# CPU.net
KiCad netlist of a schematic drawn in Altium Designer
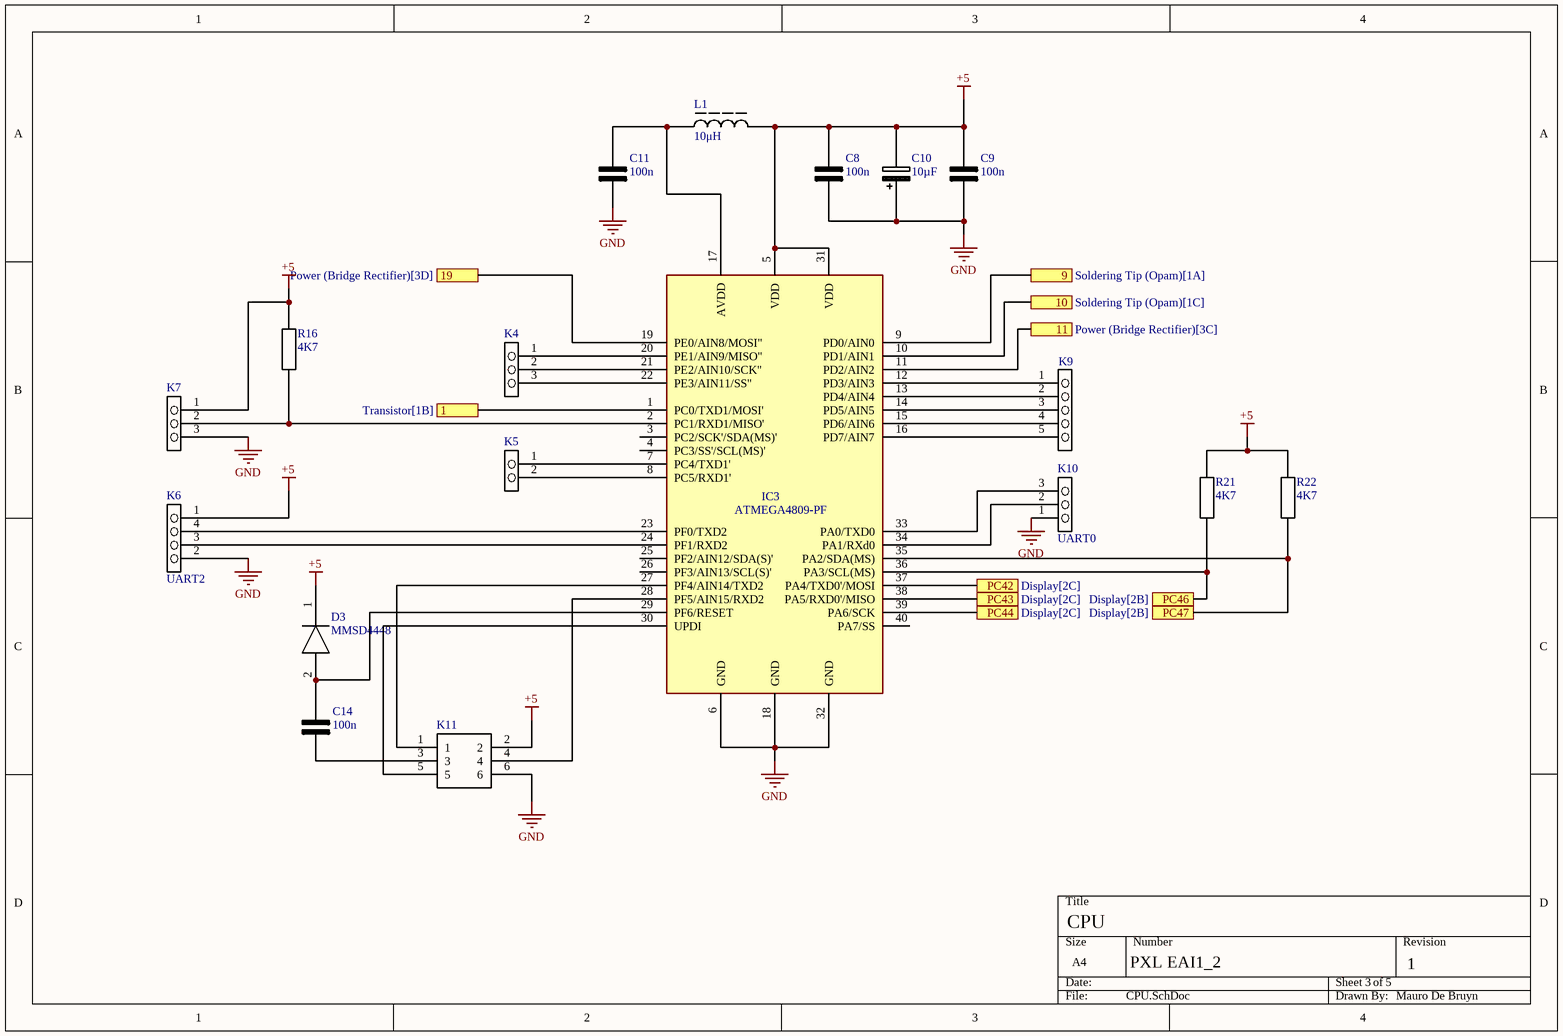
[diagram p0: CPU.SchDoc]

(export (version "E")
  (design (tool "Eeschema 10.0.6"))
  (components
    (comp (ref "C8")
      (value "100n")
      (footprint "0805")
      (description "Capacitor")
      (fields (field (name "MANUFACTURER_PART_NUMBER") "C0805C391G3GACTU"))
      (libsource (lib "SamacSys") (part "0805 (Capacitor)"))
    )
    (comp (ref "C9")
      (value "100n")
      (footprint "0805")
      (description "Capacitor")
      (fields (field (name "MANUFACTURER_PART_NUMBER") "C0805C391G3GACTU"))
      (libsource (lib "SamacSys") (part "0805 (Capacitor)"))
    )
    (comp (ref "C10")
      (value "10µF")
      (footprint "SamacSys:CAPPRD200W52D500H1250")
      (description "Capacitor Polarised")
      (fields
        (field (name "MOUSER2 PART NUMBER") "710-860020672010")
        (field (name "MANUFACTURER_PART_NUMBER") "860020672010")
      )
      (libsource (lib "SamacSys") (part "860020672010"))
    )
    (comp (ref "C11")
      (value "100n")
      (footprint "0805")
      (description "Capacitor")
      (fields (field (name "MANUFACTURER_PART_NUMBER") "C0805C391G3GACTU"))
      (libsource (lib "SamacSys") (part "0805 (Capacitor)"))
    )
    (comp (ref "C14")
      (value "100n")
      (footprint "0805")
      (description "Capacitor")
      (fields (field (name "MANUFACTURER_PART_NUMBER") "C0805C391G3GACTU"))
      (libsource (lib "SamacSys") (part "0805 (Capacitor)"))
    )
    (comp (ref "D3")
      (value "MMSD4448")
      (footprint "SamacSys:SOD3816X128N")
      (description "Diode")
      (fields (field (name "MOUSER PART NUMBER") "512-MMSD4448"))
      (libsource (lib "SamacSys") (part "MMSD4448"))
    )
    (comp (ref "IC3")
      (value "ATMEGA4809-PF")
      (footprint "SamacSys:DIP1543W58P254L5175H635Q40N")
      (description "Integrated Circuit")
      (fields (field (name "MOUSER2 PART NUMBER") "556-ATMEGA4809-PF"))
      (libsource (lib "SamacSys") (part "ATMEGA4809-PF"))
    )
    (comp (ref "K4")
      (value "M20-9990345")
      (footprint "SamacSys:HDRV3W64P0X254_1X3_762X254X864P")
      (description "Connector 3-PIN")
      (fields (field (name "MOUSER2 PART NUMBER") "855-M20-9990345"))
      (libsource (lib "SamacSys") (part "M20-9990345"))
    )
    (comp (ref "K5")
      (value "M20-9990246")
      (footprint "SamacSys:HDRV2W66P0X254_1X2_508X254X874P")
      (description "Connector 2-PIN")
      (fields (field (name "MOUSER2 PART NUMBER") "855-M20-9990246"))
      (libsource (lib "SamacSys") (part "M20-9990246"))
    )
    (comp (ref "K6")
      (value "UART2")
      (footprint "SamacSys:HDRV4W64P0X254_1X4_1016X254X834P")
      (description "Connector 4-PIN")
      (fields
        (field (name "MOUSER2 PART NUMBER") "855-M20-9770446")
        (field (name "MANUFACTURER_PART_NUMBER") "M20-9770446")
      )
      (libsource (lib "SamacSys") (part "M20-9770446"))
    )
    (comp (ref "K7")
      (value "M20-9990345")
      (footprint "SamacSys:HDRV3W64P0X254_1X3_762X254X864P")
      (description "Connector 3-PIN")
      (fields (field (name "MOUSER2 PART NUMBER") "855-M20-9990345"))
      (libsource (lib "SamacSys") (part "M20-9990345"))
    )
    (comp (ref "K9")
      (value "M20-9990545")
      (footprint "SamacSys:HDRV5W64P0X254_1X5_1270X254X864P")
      (description "Connector 5-PIN")
      (fields (field (name "MOUSER2 PART NUMBER") "855-M20-9990545"))
      (libsource (lib "SamacSys") (part "M20-9990545"))
    )
    (comp (ref "K10")
      (value "UART0")
      (footprint "SamacSys:HDRV3W64P0X254_1X3_762X254X864P")
      (description "Connector 3-PIN")
      (fields
        (field (name "MOUSER2 PART NUMBER") "855-M20-9990345")
        (field (name "MANUFACTURER_PART_NUMBER") "M20-9990345")
      )
      (libsource (lib "SamacSys") (part "M20-9990345"))
    )
    (comp (ref "K11")
      (value "M20-9760342")
      (footprint "SamacSys:HDRV6W66P254_2X3_762X508X830P")
      (description "Connector 6-PIN")
      (libsource (lib "SamacSys") (part "M20-9760342"))
    )
    (comp (ref "L1")
      (value "10μH")
      (footprint "SamacSys:VLS56045")
      (description "Inductor")
      (fields
        (field (name "MOUSER2 PART NUMBER") "810-VLS6045EX-100M-H")
        (field (name "MANUFACTURER_PART_NUMBER") "VLS6045EX-100M-H")
      )
      (libsource (lib "SamacSys") (part "VLS6045EX-100M-H"))
    )
    (comp (ref "R16")
      (value "4K7")
      (footprint "0805")
      (description "Resistor")
      (fields (field (name "MANUFACTURER_PART_NUMBER") "C0805C391G3GACTU"))
      (libsource (lib "SamacSys") (part "0805 (Resistor)"))
    )
    (comp (ref "R21")
      (value "4K7")
      (footprint "0805")
      (description "Resistor")
      (fields (field (name "MANUFACTURER_PART_NUMBER") "C0805C391G3GACTU"))
      (libsource (lib "SamacSys") (part "0805 (Resistor)"))
    )
    (comp (ref "R22")
      (value "4K7")
      (footprint "0805")
      (description "Resistor")
      (fields (field (name "MANUFACTURER_PART_NUMBER") "C0805C391G3GACTU"))
      (libsource (lib "SamacSys") (part "0805 (Resistor)"))
    )
  )
  (nets
    (net (code "1") (name "+5") (class "Default")
      (node (ref "C10") (pin "2") (pinfunction "-_2") (pintype "passive"))
      (node (ref "C8") (pin "2") (pinfunction "-_2") (pintype "passive"))
      (node (ref "C9") (pin "2") (pinfunction "-_2") (pintype "passive"))
      (node (ref "D3") (pin "1") (pinfunction "K_1") (pintype "passive"))
      (node (ref "IC3") (pin "31") (pinfunction "VDD_31") (pintype "passive"))
      (node (ref "IC3") (pin "5") (pinfunction "VDD_5") (pintype "passive"))
      (node (ref "K11") (pin "2") (pinfunction "2_2") (pintype "passive"))
      (node (ref "K6") (pin "1") (pinfunction "1_1") (pintype "passive"))
      (node (ref "K7") (pin "1") (pinfunction "1_1") (pintype "passive"))
      (node (ref "L1") (pin "2") (pinfunction "2_2") (pintype "passive"))
      (node (ref "R16") (pin "2") (pinfunction "2_2") (pintype "passive"))
      (node (ref "R21") (pin "2") (pinfunction "2_2") (pintype "passive"))
      (node (ref "R22") (pin "2") (pinfunction "2_2") (pintype "passive"))
    )
    (net (code "2") (name "/1") (class "Default")
      (node (ref "IC3") (pin "1") (pinfunction "PC0/TXD1/MOSI'_1") (pintype "passive"))
    )
    (net (code "3") (name "/9") (class "Default")
      (node (ref "IC3") (pin "9") (pinfunction "PD0/AIN0_9") (pintype "passive"))
    )
    (net (code "4") (name "/10") (class "Default")
      (node (ref "IC3") (pin "10") (pinfunction "PD1/AIN1_10") (pintype "passive"))
    )
    (net (code "5") (name "/11") (class "Default")
      (node (ref "IC3") (pin "11") (pinfunction "PD2/AIN2_11") (pintype "passive"))
    )
    (net (code "6") (name "/19") (class "Default")
      (node (ref "IC3") (pin "19") (pinfunction "PE0/AIN8/MOSI\"_19") (pintype "passive"))
    )
    (net (code "7") (name "/PC42") (class "Default")
      (node (ref "IC3") (pin "37") (pinfunction "PA4/TXD0'/MOSI_37") (pintype "passive"))
    )
    (net (code "8") (name "/PC43") (class "Default")
      (node (ref "IC3") (pin "38") (pinfunction "PA5/RXD0'/MISO_38") (pintype "passive"))
    )
    (net (code "9") (name "/PC44") (class "Default")
      (node (ref "IC3") (pin "39") (pinfunction "PA6/SCK_39") (pintype "passive"))
    )
    (net (code "10") (name "/PC46") (class "Default")
      (node (ref "IC3") (pin "36") (pinfunction "PA3/SCL(MS)_36") (pintype "passive"))
      (node (ref "R21") (pin "1") (pinfunction "1_1") (pintype "passive"))
    )
    (net (code "11") (name "/PC47") (class "Default")
      (node (ref "IC3") (pin "35") (pinfunction "PA2/SDA(MS)_35") (pintype "passive"))
      (node (ref "R22") (pin "1") (pinfunction "1_1") (pintype "passive"))
    )
    (net (code "12") (name "GND") (class "Default")
      (node (ref "C10") (pin "1") (pinfunction "+_1") (pintype "passive"))
      (node (ref "C11") (pin "1") (pinfunction "+_1") (pintype "passive"))
      (node (ref "C8") (pin "1") (pinfunction "+_1") (pintype "passive"))
      (node (ref "C9") (pin "1") (pinfunction "+_1") (pintype "passive"))
      (node (ref "IC3") (pin "18") (pinfunction "GND_18") (pintype "passive"))
      (node (ref "IC3") (pin "32") (pinfunction "GND_32") (pintype "passive"))
      (node (ref "IC3") (pin "6") (pinfunction "GND_6") (pintype "passive"))
      (node (ref "K10") (pin "1") (pinfunction "1_1") (pintype "passive"))
      (node (ref "K11") (pin "6") (pinfunction "6_6") (pintype "passive"))
      (node (ref "K6") (pin "2") (pinfunction "2_2") (pintype "passive"))
      (node (ref "K7") (pin "3") (pinfunction "3_3") (pintype "passive"))
    )
    (net (code "13") (name "Net-(C11--)") (class "Default")
      (node (ref "C11") (pin "2") (pinfunction "-_2") (pintype "passive"))
      (node (ref "IC3") (pin "17") (pinfunction "AVDD_17") (pintype "passive"))
      (node (ref "L1") (pin "1") (pinfunction "1_1") (pintype "passive"))
    )
    (net (code "14") (name "Net-(C14-+)") (class "Default")
      (node (ref "C14") (pin "1") (pinfunction "+_1") (pintype "passive"))
      (node (ref "K11") (pin "3") (pinfunction "3_3") (pintype "passive"))
    )
    (net (code "15") (name "Net-(C14--)") (class "Default")
      (node (ref "C14") (pin "2") (pinfunction "-_2") (pintype "passive"))
      (node (ref "D3") (pin "2") (pinfunction "A_2") (pintype "passive"))
      (node (ref "IC3") (pin "29") (pinfunction "PF6/RESET_29") (pintype "passive"))
    )
    (net (code "16") (name "Net-(IC3-PA0{slash}TXD0)") (class "Default")
      (node (ref "IC3") (pin "33") (pinfunction "PA0/TXD0_33") (pintype "passive"))
      (node (ref "K10") (pin "3") (pinfunction "3_3") (pintype "passive"))
    )
    (net (code "17") (name "Net-(IC3-PA1{slash}RXd0)") (class "Default")
      (node (ref "IC3") (pin "34") (pinfunction "PA1/RXd0_34") (pintype "passive"))
      (node (ref "K10") (pin "2") (pinfunction "2_2") (pintype "passive"))
    )
    (net (code "18") (name "Net-(IC3-PC1{slash}RXD1{slash}MISO')") (class "Default")
      (node (ref "IC3") (pin "2") (pinfunction "PC1/RXD1/MISO'_2") (pintype "passive"))
      (node (ref "K7") (pin "2") (pinfunction "2_2") (pintype "passive"))
      (node (ref "R16") (pin "1") (pinfunction "1_1") (pintype "passive"))
    )
    (net (code "19") (name "Net-(IC3-PC4{slash}TXD1')") (class "Default")
      (node (ref "IC3") (pin "7") (pinfunction "PC4/TXD1'_7") (pintype "passive"))
      (node (ref "K5") (pin "1") (pinfunction "1_1") (pintype "passive"))
    )
    (net (code "20") (name "Net-(IC3-PC5{slash}RXD1')") (class "Default")
      (node (ref "IC3") (pin "8") (pinfunction "PC5/RXD1'_8") (pintype "passive"))
      (node (ref "K5") (pin "2") (pinfunction "2_2") (pintype "passive"))
    )
    (net (code "21") (name "Net-(IC3-PD3{slash}AIN3)") (class "Default")
      (node (ref "IC3") (pin "12") (pinfunction "PD3/AIN3_12") (pintype "passive"))
      (node (ref "K9") (pin "1") (pinfunction "1_1") (pintype "passive"))
    )
    (net (code "22") (name "Net-(IC3-PD4{slash}AIN4)") (class "Default")
      (node (ref "IC3") (pin "13") (pinfunction "PD4/AIN4_13") (pintype "passive"))
      (node (ref "K9") (pin "2") (pinfunction "2_2") (pintype "passive"))
    )
    (net (code "23") (name "Net-(IC3-PD5{slash}AIN5)") (class "Default")
      (node (ref "IC3") (pin "14") (pinfunction "PD5/AIN5_14") (pintype "passive"))
      (node (ref "K9") (pin "3") (pinfunction "3_3") (pintype "passive"))
    )
    (net (code "24") (name "Net-(IC3-PD6{slash}AIN6)") (class "Default")
      (node (ref "IC3") (pin "15") (pinfunction "PD6/AIN6_15") (pintype "passive"))
      (node (ref "K9") (pin "4") (pinfunction "4_4") (pintype "passive"))
    )
    (net (code "25") (name "Net-(IC3-PD7{slash}AIN7)") (class "Default")
      (node (ref "IC3") (pin "16") (pinfunction "PD7/AIN7_16") (pintype "passive"))
      (node (ref "K9") (pin "5") (pinfunction "5_5") (pintype "passive"))
    )
    (net (code "26") (name "Net-(IC3-PE1{slash}AIN9{slash}MISO\")") (class "Default")
      (node (ref "IC3") (pin "20") (pinfunction "PE1/AIN9/MISO\"_20") (pintype "passive"))
      (node (ref "K4") (pin "1") (pinfunction "1_1") (pintype "passive"))
    )
    (net (code "27") (name "Net-(IC3-PE2{slash}AIN10{slash}SCK\")") (class "Default")
      (node (ref "IC3") (pin "21") (pinfunction "PE2/AIN10/SCK\"_21") (pintype "passive"))
      (node (ref "K4") (pin "2") (pinfunction "2_2") (pintype "passive"))
    )
    (net (code "28") (name "Net-(IC3-PE3{slash}AIN11{slash}SS\")") (class "Default")
      (node (ref "IC3") (pin "22") (pinfunction "PE3/AIN11/SS\"_22") (pintype "passive"))
      (node (ref "K4") (pin "3") (pinfunction "3_3") (pintype "passive"))
    )
    (net (code "29") (name "Net-(IC3-PF0{slash}TXD2)") (class "Default")
      (node (ref "IC3") (pin "23") (pinfunction "PF0/TXD2_23") (pintype "passive"))
      (node (ref "K6") (pin "4") (pinfunction "4_4") (pintype "passive"))
    )
    (net (code "30") (name "Net-(IC3-PF1{slash}RXD2)") (class "Default")
      (node (ref "IC3") (pin "24") (pinfunction "PF1/RXD2_24") (pintype "passive"))
      (node (ref "K6") (pin "3") (pinfunction "3_3") (pintype "passive"))
    )
    (net (code "31") (name "Net-(IC3-PF4{slash}AIN14{slash}TXD2)") (class "Default")
      (node (ref "IC3") (pin "27") (pinfunction "PF4/AIN14/TXD2_27") (pintype "passive"))
      (node (ref "K11") (pin "1") (pinfunction "1_1") (pintype "passive"))
    )
    (net (code "32") (name "Net-(IC3-PF5{slash}AIN15{slash}RXD2)") (class "Default")
      (node (ref "IC3") (pin "28") (pinfunction "PF5/AIN15/RXD2_28") (pintype "passive"))
      (node (ref "K11") (pin "4") (pinfunction "4_4") (pintype "passive"))
    )
    (net (code "33") (name "Net-(IC3-UPDI)") (class "Default")
      (node (ref "IC3") (pin "30") (pinfunction "UPDI_30") (pintype "passive"))
      (node (ref "K11") (pin "5") (pinfunction "5_5") (pintype "passive"))
    )
    (net (code "34") (name "unconnected-(IC3-PA7{slash}SS-Pad40)") (class "Default")
      (node (ref "IC3") (pin "40") (pinfunction "PA7/SS_40") (pintype "passive"))
    )
    (net (code "35") (name "unconnected-(IC3-PC2{slash}SCK'{slash}SDA(MS)'-Pad3)") (class "Default")
      (node (ref "IC3") (pin "3") (pinfunction "PC2/SCK'/SDA(MS)'_3") (pintype "passive"))
    )
    (net (code "36") (name "unconnected-(IC3-PC3{slash}SS'{slash}SCL(MS)'-Pad4)") (class "Default")
      (node (ref "IC3") (pin "4") (pinfunction "PC3/SS'/SCL(MS)'_4") (pintype "passive"))
    )
    (net (code "37") (name "unconnected-(IC3-PF2{slash}AIN12{slash}SDA(S)'-Pad25)") (class "Default")
      (node (ref "IC3") (pin "25") (pinfunction "PF2/AIN12/SDA(S)'_25") (pintype "passive"))
    )
    (net (code "38") (name "unconnected-(IC3-PF3{slash}AIN13{slash}SCL(S)'-Pad26)") (class "Default")
      (node (ref "IC3") (pin "26") (pinfunction "PF3/AIN13/SCL(S)'_26") (pintype "passive"))
    )
  )
)
